# sch_mk32_dsd_2022-03-23.net
KiCad netlist of a schematic drawn in Altium Designer
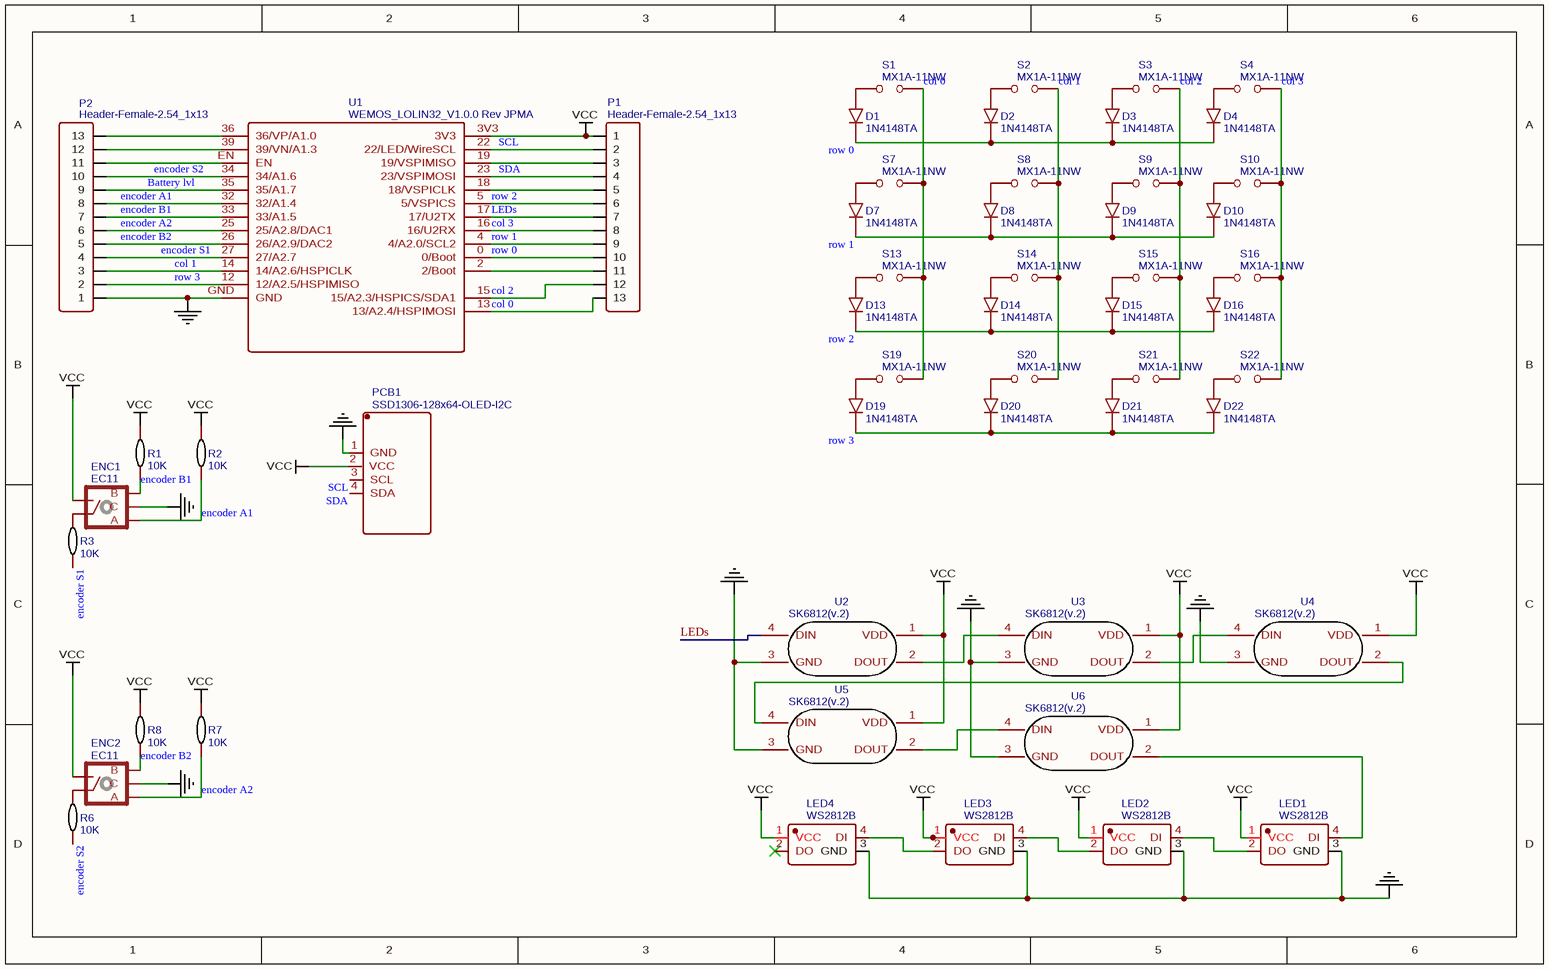
[diagram p0: sch_mk32_dsd_2022-03-23.schdoc]

(export (version "E")
  (design (tool "Eeschema 10.0.6"))
  (components
    (comp (ref "D1")
      (value "1N4148TA")
      (footprint "DO-35")
      (fields (field (name "BOM_SUPPLIER PART") "C124481") (field (name "CONTRIBUTOR") "LCSC"))
      (libsource (lib "altium-import") (part "root_3_1N4148TA_"))
    )
    (comp (ref "D2")
      (value "1N4148TA")
      (footprint "DO-35")
      (fields (field (name "BOM_SUPPLIER PART") "C124481") (field (name "CONTRIBUTOR") "LCSC"))
      (libsource (lib "altium-import") (part "root_3_1N4148TA_"))
    )
    (comp (ref "D3")
      (value "1N4148TA")
      (footprint "DO-35")
      (fields (field (name "BOM_SUPPLIER PART") "C124481") (field (name "CONTRIBUTOR") "LCSC"))
      (libsource (lib "altium-import") (part "root_3_1N4148TA_"))
    )
    (comp (ref "D4")
      (value "1N4148TA")
      (footprint "DO-35")
      (fields (field (name "BOM_SUPPLIER PART") "C124481") (field (name "CONTRIBUTOR") "LCSC"))
      (libsource (lib "altium-import") (part "root_3_1N4148TA_"))
    )
    (comp (ref "D7")
      (value "1N4148TA")
      (footprint "DO-35")
      (fields (field (name "BOM_SUPPLIER PART") "C124481") (field (name "CONTRIBUTOR") "LCSC"))
      (libsource (lib "altium-import") (part "root_3_1N4148TA_"))
    )
    (comp (ref "D8")
      (value "1N4148TA")
      (footprint "DO-35")
      (fields (field (name "BOM_SUPPLIER PART") "C124481") (field (name "CONTRIBUTOR") "LCSC"))
      (libsource (lib "altium-import") (part "root_3_1N4148TA_"))
    )
    (comp (ref "D9")
      (value "1N4148TA")
      (footprint "DO-35")
      (fields (field (name "BOM_SUPPLIER PART") "C124481") (field (name "CONTRIBUTOR") "LCSC"))
      (libsource (lib "altium-import") (part "root_3_1N4148TA_"))
    )
    (comp (ref "D10")
      (value "1N4148TA")
      (footprint "DO-35")
      (fields (field (name "BOM_SUPPLIER PART") "C124481") (field (name "CONTRIBUTOR") "LCSC"))
      (libsource (lib "altium-import") (part "root_3_1N4148TA_"))
    )
    (comp (ref "D13")
      (value "1N4148TA")
      (footprint "DO-35")
      (fields (field (name "BOM_SUPPLIER PART") "C124481") (field (name "CONTRIBUTOR") "LCSC"))
      (libsource (lib "altium-import") (part "root_3_1N4148TA_"))
    )
    (comp (ref "D14")
      (value "1N4148TA")
      (footprint "DO-35")
      (fields (field (name "BOM_SUPPLIER PART") "C124481") (field (name "CONTRIBUTOR") "LCSC"))
      (libsource (lib "altium-import") (part "root_3_1N4148TA_"))
    )
    (comp (ref "D15")
      (value "1N4148TA")
      (footprint "DO-35")
      (fields (field (name "BOM_SUPPLIER PART") "C124481") (field (name "CONTRIBUTOR") "LCSC"))
      (libsource (lib "altium-import") (part "root_3_1N4148TA_"))
    )
    (comp (ref "D16")
      (value "1N4148TA")
      (footprint "DO-35")
      (fields (field (name "BOM_SUPPLIER PART") "C124481") (field (name "CONTRIBUTOR") "LCSC"))
      (libsource (lib "altium-import") (part "root_3_1N4148TA_"))
    )
    (comp (ref "D19")
      (value "1N4148TA")
      (footprint "DO-35")
      (fields (field (name "BOM_SUPPLIER PART") "C124481") (field (name "CONTRIBUTOR") "LCSC"))
      (libsource (lib "altium-import") (part "root_3_1N4148TA_"))
    )
    (comp (ref "D20")
      (value "1N4148TA")
      (footprint "DO-35")
      (fields (field (name "BOM_SUPPLIER PART") "C124481") (field (name "CONTRIBUTOR") "LCSC"))
      (libsource (lib "altium-import") (part "root_3_1N4148TA_"))
    )
    (comp (ref "D21")
      (value "1N4148TA")
      (footprint "DO-35")
      (fields (field (name "BOM_SUPPLIER PART") "C124481") (field (name "CONTRIBUTOR") "LCSC"))
      (libsource (lib "altium-import") (part "root_3_1N4148TA_"))
    )
    (comp (ref "D22")
      (value "1N4148TA")
      (footprint "DO-35")
      (fields (field (name "BOM_SUPPLIER PART") "C124481") (field (name "CONTRIBUTOR") "LCSC"))
      (libsource (lib "altium-import") (part "root_3_1N4148TA_"))
    )
    (comp (ref "ENC1")
      (value "EC11")
      (footprint "EC11")
      (fields (field (name "BOM_MANUFACTURER PART") "?"))
      (libsource (lib "altium-import") (part "root_0_EC11_"))
    )
    (comp (ref "ENC2")
      (value "EC11")
      (footprint "EC11")
      (fields (field (name "BOM_MANUFACTURER PART") "?"))
      (libsource (lib "altium-import") (part "root_0_EC11_"))
    )
    (comp (ref "LED1")
      (value "WS2812B")
      (footprint "WS2812B-MIRROR")
      (fields (field (name "CONTRIBUTOR") "ridgy"))
      (libsource (lib "") (part "root_0_WS2812B__2"))
    )
    (comp (ref "LED2")
      (value "WS2812B")
      (footprint "WS2812B-MIRROR")
      (fields (field (name "CONTRIBUTOR") "ridgy"))
      (libsource (lib "altium-import") (part "root_0_WS2812B_"))
    )
    (comp (ref "LED3")
      (value "WS2812B")
      (footprint "WS2812B-MIRROR")
      (fields (field (name "CONTRIBUTOR") "ridgy"))
      (libsource (lib "") (part "root_0_WS2812B__1"))
    )
    (comp (ref "LED4")
      (value "WS2812B")
      (footprint "WS2812B-MIRROR")
      (fields (field (name "CONTRIBUTOR") "ridgy"))
      (libsource (lib "") (part "root_0_WS2812B__2"))
    )
    (comp (ref "P1")
      (value "Header-Female-2.54_1x13")
      (footprint "HDR-13X1/2.54")
      (fields
        (field (name "BOM_MANUFACTURER PART") "Female header 2.54-1*13P")
        (field (name "BOM_SUPPLIER PART") "C52709")
        (field (name "CONTRIBUTOR") "LCSC")
      )
      (libsource (lib "altium-import") (part "root_0_Header-Female-2.54_1x13_"))
    )
    (comp (ref "P2")
      (value "Header-Female-2.54_1x13")
      (footprint "HDR-13X1/2.54")
      (fields
        (field (name "BOM_MANUFACTURER PART") "Female header 2.54-1*13P")
        (field (name "BOM_SUPPLIER PART") "C52709")
        (field (name "CONTRIBUTOR") "LCSC")
      )
      (libsource (lib "altium-import") (part "root_2_Header-Female-2.54_1x13_"))
    )
    (comp (ref "PCB1")
      (value "SSD1306-128x64-OLED-I2C")
      (footprint "SSD1306_GNDVCC")
      (fields (field (name "BOM_MANUFACTURER PART") "?"))
      (libsource (lib "altium-import") (part "root_0_SSD1306-128x64-OLED-I2C_"))
    )
    (comp (ref "R1")
      (value "10K")
      (footprint "R03")
      (fields (field (name "BOM_MANUFACTURER PART") "?") (field (name "CONTRIBUTOR") "sorinfxdx"))
      (libsource (lib "altium-import") (part "root_0_10K_"))
    )
    (comp (ref "R2")
      (value "10K")
      (footprint "R03")
      (fields (field (name "BOM_MANUFACTURER PART") "?") (field (name "CONTRIBUTOR") "sorinfxdx"))
      (libsource (lib "altium-import") (part "root_0_10K_"))
    )
    (comp (ref "R3")
      (value "10K")
      (footprint "R03")
      (fields (field (name "BOM_MANUFACTURER PART") "?") (field (name "CONTRIBUTOR") "sorinfxdx"))
      (libsource (lib "altium-import") (part "root_0_10K_"))
    )
    (comp (ref "R6")
      (value "10K")
      (footprint "R03")
      (fields (field (name "BOM_MANUFACTURER PART") "?") (field (name "CONTRIBUTOR") "sorinfxdx"))
      (libsource (lib "altium-import") (part "root_0_10K_"))
    )
    (comp (ref "R7")
      (value "10K")
      (footprint "R03")
      (fields (field (name "BOM_MANUFACTURER PART") "?") (field (name "CONTRIBUTOR") "sorinfxdx"))
      (libsource (lib "altium-import") (part "root_0_10K_"))
    )
    (comp (ref "R8")
      (value "10K")
      (footprint "R03")
      (fields (field (name "BOM_MANUFACTURER PART") "?") (field (name "CONTRIBUTOR") "sorinfxdx"))
      (libsource (lib "altium-import") (part "root_0_10K_"))
    )
    (comp (ref "S1")
      (value "MX1A-11NW")
      (footprint "MX1A")
      (fields (field (name "BOM_SUPPLIER PART") "540-MX1A-11NW"))
      (libsource (lib "altium-import") (part "root_0_MX1A-11NW_"))
    )
    (comp (ref "S2")
      (value "MX1A-11NW")
      (footprint "MX1A")
      (fields (field (name "BOM_SUPPLIER PART") "540-MX1A-11NW"))
      (libsource (lib "altium-import") (part "root_0_MX1A-11NW_"))
    )
    (comp (ref "S3")
      (value "MX1A-11NW")
      (footprint "MX1A")
      (fields (field (name "BOM_SUPPLIER PART") "540-MX1A-11NW"))
      (libsource (lib "altium-import") (part "root_0_MX1A-11NW_"))
    )
    (comp (ref "S4")
      (value "MX1A-11NW")
      (footprint "MX1A")
      (fields (field (name "BOM_SUPPLIER PART") "540-MX1A-11NW"))
      (libsource (lib "altium-import") (part "root_0_MX1A-11NW_"))
    )
    (comp (ref "S7")
      (value "MX1A-11NW")
      (footprint "MX1A")
      (fields (field (name "BOM_SUPPLIER PART") "540-MX1A-11NW"))
      (libsource (lib "altium-import") (part "root_0_MX1A-11NW_"))
    )
    (comp (ref "S8")
      (value "MX1A-11NW")
      (footprint "MX1A")
      (fields (field (name "BOM_SUPPLIER PART") "540-MX1A-11NW"))
      (libsource (lib "altium-import") (part "root_0_MX1A-11NW_"))
    )
    (comp (ref "S9")
      (value "MX1A-11NW")
      (footprint "MX1A")
      (fields (field (name "BOM_SUPPLIER PART") "540-MX1A-11NW"))
      (libsource (lib "altium-import") (part "root_0_MX1A-11NW_"))
    )
    (comp (ref "S10")
      (value "MX1A-11NW")
      (footprint "MX1A")
      (fields (field (name "BOM_SUPPLIER PART") "540-MX1A-11NW"))
      (libsource (lib "altium-import") (part "root_0_MX1A-11NW_"))
    )
    (comp (ref "S13")
      (value "MX1A-11NW")
      (footprint "MX1A")
      (fields (field (name "BOM_SUPPLIER PART") "540-MX1A-11NW"))
      (libsource (lib "altium-import") (part "root_0_MX1A-11NW_"))
    )
    (comp (ref "S14")
      (value "MX1A-11NW")
      (footprint "MX1A")
      (fields (field (name "BOM_SUPPLIER PART") "540-MX1A-11NW"))
      (libsource (lib "altium-import") (part "root_0_MX1A-11NW_"))
    )
    (comp (ref "S15")
      (value "MX1A-11NW")
      (footprint "MX1A")
      (fields (field (name "BOM_SUPPLIER PART") "540-MX1A-11NW"))
      (libsource (lib "altium-import") (part "root_0_MX1A-11NW_"))
    )
    (comp (ref "S16")
      (value "MX1A-11NW")
      (footprint "MX1A")
      (fields (field (name "BOM_SUPPLIER PART") "540-MX1A-11NW"))
      (libsource (lib "altium-import") (part "root_0_MX1A-11NW_"))
    )
    (comp (ref "S19")
      (value "MX1A-11NW")
      (footprint "MX1A")
      (fields (field (name "BOM_SUPPLIER PART") "540-MX1A-11NW"))
      (libsource (lib "altium-import") (part "root_0_MX1A-11NW_"))
    )
    (comp (ref "S20")
      (value "MX1A-11NW")
      (footprint "MX1A")
      (fields (field (name "BOM_SUPPLIER PART") "540-MX1A-11NW"))
      (libsource (lib "altium-import") (part "root_0_MX1A-11NW_"))
    )
    (comp (ref "S21")
      (value "MX1A-11NW")
      (footprint "MX1A")
      (fields (field (name "BOM_SUPPLIER PART") "540-MX1A-11NW"))
      (libsource (lib "altium-import") (part "root_0_MX1A-11NW_"))
    )
    (comp (ref "S22")
      (value "MX1A-11NW")
      (footprint "MX1A")
      (fields (field (name "BOM_SUPPLIER PART") "540-MX1A-11NW"))
      (libsource (lib "altium-import") (part "root_0_MX1A-11NW_"))
    )
    (comp (ref "U1")
      (value "WEMOS_LOLIN32_V1.0.0 Rev JPMA")
      (footprint "WEMOS LOLIN32 LITE V1.0.0 UC")
      (fields (field (name "BOM_MANUFACTURER PART") "?") (field (name "CONTRIBUTOR") "JPMA"))
      (libsource (lib "altium-import") (part "root_0_WEMOS_LOLIN32_V1.0.0 Rev JPMA_"))
    )
    (comp (ref "U2")
      (value "SK6812(v.2)")
      (footprint "SK6812MINI-E")
      (fields (field (name "CONTRIBUTOR") "PetrSlachta"))
      (libsource (lib "altium-import") (part "root_0_SK6812(v.2)_"))
    )
    (comp (ref "U3")
      (value "SK6812(v.2)")
      (footprint "SK6812MINI-E")
      (fields (field (name "CONTRIBUTOR") "PetrSlachta"))
      (libsource (lib "altium-import") (part "root_0_SK6812(v.2)_"))
    )
    (comp (ref "U4")
      (value "SK6812(v.2)")
      (footprint "SK6812MINI-E")
      (fields (field (name "CONTRIBUTOR") "PetrSlachta"))
      (libsource (lib "altium-import") (part "root_0_SK6812(v.2)_"))
    )
    (comp (ref "U5")
      (value "SK6812(v.2)")
      (footprint "SK6812MINI-E")
      (fields (field (name "CONTRIBUTOR") "PetrSlachta"))
      (libsource (lib "altium-import") (part "root_0_SK6812(v.2)_"))
    )
    (comp (ref "U6")
      (value "SK6812(v.2)")
      (footprint "SK6812MINI-E")
      (fields (field (name "CONTRIBUTOR") "PetrSlachta"))
      (libsource (lib "altium-import") (part "root_0_SK6812(v.2)_"))
    )
  )
  (nets
    (net (code "1") (name "/Battery lvl") (class "Default")
      (node (ref "P2") (pin "9") (pinfunction "9_9") (pintype "passive"))
      (node (ref "U1") (pin "35") (pinfunction "35/A1.7_35") (pintype "passive"))
    )
    (net (code "2") (name "/LEDs") (class "Default")
      (node (ref "P1") (pin "7") (pinfunction "7_7") (pintype "passive"))
      (node (ref "U1") (pin "17") (pinfunction "17/U2TX_17") (pintype "passive"))
      (node (ref "U2") (pin "4") (pinfunction "DIN_4") (pintype "passive"))
    )
    (net (code "3") (name "/SCL") (class "Default")
      (node (ref "P1") (pin "2") (pinfunction "2_2") (pintype "passive"))
      (node (ref "PCB1") (pin "3") (pinfunction "SCL_3") (pintype "passive"))
      (node (ref "U1") (pin "22") (pinfunction "22/LED/WireSCL_22") (pintype "passive"))
    )
    (net (code "4") (name "/SDA") (class "Default")
      (node (ref "P1") (pin "4") (pinfunction "4_4") (pintype "passive"))
      (node (ref "PCB1") (pin "4") (pinfunction "SDA_4") (pintype "passive"))
      (node (ref "U1") (pin "23") (pinfunction "23/VSPIMOSI_23") (pintype "passive"))
    )
    (net (code "5") (name "/col 0") (class "Default")
      (node (ref "P1") (pin "13") (pinfunction "13_13") (pintype "passive"))
      (node (ref "S1") (pin "2") (pinfunction "2_2") (pintype "passive"))
      (node (ref "S13") (pin "2") (pinfunction "2_2") (pintype "passive"))
      (node (ref "S19") (pin "2") (pinfunction "2_2") (pintype "passive"))
      (node (ref "S7") (pin "2") (pinfunction "2_2") (pintype "passive"))
      (node (ref "U1") (pin "13") (pinfunction "13/A2.4/HSPIMOSI_13") (pintype "passive"))
    )
    (net (code "6") (name "/col 1") (class "Default")
      (node (ref "P2") (pin "3") (pinfunction "3_3") (pintype "passive"))
      (node (ref "S14") (pin "2") (pinfunction "2_2") (pintype "passive"))
      (node (ref "S2") (pin "2") (pinfunction "2_2") (pintype "passive"))
      (node (ref "S20") (pin "2") (pinfunction "2_2") (pintype "passive"))
      (node (ref "S8") (pin "2") (pinfunction "2_2") (pintype "passive"))
      (node (ref "U1") (pin "14") (pinfunction "14/A2.6/HSPICLK_14") (pintype "passive"))
    )
    (net (code "7") (name "/col 2") (class "Default")
      (node (ref "P1") (pin "12") (pinfunction "12_12") (pintype "passive"))
      (node (ref "S15") (pin "2") (pinfunction "2_2") (pintype "passive"))
      (node (ref "S21") (pin "2") (pinfunction "2_2") (pintype "passive"))
      (node (ref "S3") (pin "2") (pinfunction "2_2") (pintype "passive"))
      (node (ref "S9") (pin "2") (pinfunction "2_2") (pintype "passive"))
      (node (ref "U1") (pin "15") (pinfunction "15/A2.3/HSPICS/SDA1_15") (pintype "passive"))
    )
    (net (code "8") (name "/col 3") (class "Default")
      (node (ref "P1") (pin "8") (pinfunction "8_8") (pintype "passive"))
      (node (ref "S10") (pin "2") (pinfunction "2_2") (pintype "passive"))
      (node (ref "S16") (pin "2") (pinfunction "2_2") (pintype "passive"))
      (node (ref "S22") (pin "2") (pinfunction "2_2") (pintype "passive"))
      (node (ref "S4") (pin "2") (pinfunction "2_2") (pintype "passive"))
      (node (ref "U1") (pin "16") (pinfunction "16/U2RX_16") (pintype "passive"))
    )
    (net (code "9") (name "/encoder A1") (class "Default")
      (node (ref "ENC1") (pin "3") (pinfunction "A_3") (pintype "passive"))
      (node (ref "P2") (pin "8") (pinfunction "8_8") (pintype "passive"))
      (node (ref "R2") (pin "2") (pinfunction "2_2") (pintype "passive"))
      (node (ref "U1") (pin "32") (pinfunction "32/A1.4_32") (pintype "passive"))
    )
    (net (code "10") (name "/encoder A2") (class "Default")
      (node (ref "ENC2") (pin "3") (pinfunction "A_3") (pintype "passive"))
      (node (ref "P2") (pin "6") (pinfunction "6_6") (pintype "passive"))
      (node (ref "R7") (pin "2") (pinfunction "2_2") (pintype "passive"))
      (node (ref "U1") (pin "25") (pinfunction "25/A2.8/DAC1_25") (pintype "passive"))
    )
    (net (code "11") (name "/encoder B1") (class "Default")
      (node (ref "ENC1") (pin "4") (pinfunction "B_4") (pintype "passive"))
      (node (ref "P2") (pin "7") (pinfunction "7_7") (pintype "passive"))
      (node (ref "R1") (pin "2") (pinfunction "2_2") (pintype "passive"))
      (node (ref "U1") (pin "33") (pinfunction "33/A1.5_33") (pintype "passive"))
    )
    (net (code "12") (name "/encoder B2") (class "Default")
      (node (ref "ENC2") (pin "4") (pinfunction "B_4") (pintype "passive"))
      (node (ref "P2") (pin "5") (pinfunction "5_5") (pintype "passive"))
      (node (ref "R8") (pin "2") (pinfunction "2_2") (pintype "passive"))
      (node (ref "U1") (pin "26") (pinfunction "26/A2.9/DAC2_26") (pintype "passive"))
    )
    (net (code "13") (name "/encoder S1") (class "Default")
      (node (ref "P2") (pin "4") (pinfunction "4_4") (pintype "passive"))
      (node (ref "R3") (pin "2") (pinfunction "2_2") (pintype "passive"))
      (node (ref "U1") (pin "27") (pinfunction "27/A2.7_27") (pintype "passive"))
    )
    (net (code "14") (name "/encoder S2") (class "Default")
      (node (ref "P2") (pin "10") (pinfunction "10_10") (pintype "passive"))
      (node (ref "R6") (pin "2") (pinfunction "2_2") (pintype "passive"))
      (node (ref "U1") (pin "34") (pinfunction "34/A1.6_34") (pintype "passive"))
    )
    (net (code "15") (name "/row 0") (class "Default")
      (node (ref "D1") (pin "2") (pinfunction "2_2") (pintype "passive"))
      (node (ref "D2") (pin "2") (pinfunction "2_2") (pintype "passive"))
      (node (ref "D3") (pin "2") (pinfunction "2_2") (pintype "passive"))
      (node (ref "D4") (pin "2") (pinfunction "2_2") (pintype "passive"))
      (node (ref "P1") (pin "10") (pinfunction "10_10") (pintype "passive"))
      (node (ref "U1") (pin "0") (pinfunction "0/Boot_0") (pintype "passive"))
    )
    (net (code "16") (name "/row 1") (class "Default")
      (node (ref "D10") (pin "2") (pinfunction "2_2") (pintype "passive"))
      (node (ref "D7") (pin "2") (pinfunction "2_2") (pintype "passive"))
      (node (ref "D8") (pin "2") (pinfunction "2_2") (pintype "passive"))
      (node (ref "D9") (pin "2") (pinfunction "2_2") (pintype "passive"))
      (node (ref "P1") (pin "9") (pinfunction "9_9") (pintype "passive"))
      (node (ref "U1") (pin "4") (pinfunction "4/A2.0/SCL2_4") (pintype "passive"))
    )
    (net (code "17") (name "/row 2") (class "Default")
      (node (ref "D13") (pin "2") (pinfunction "2_2") (pintype "passive"))
      (node (ref "D14") (pin "2") (pinfunction "2_2") (pintype "passive"))
      (node (ref "D15") (pin "2") (pinfunction "2_2") (pintype "passive"))
      (node (ref "D16") (pin "2") (pinfunction "2_2") (pintype "passive"))
      (node (ref "P1") (pin "6") (pinfunction "6_6") (pintype "passive"))
      (node (ref "U1") (pin "5") (pinfunction "5/VSPICS_5") (pintype "passive"))
    )
    (net (code "18") (name "/row 3") (class "Default")
      (node (ref "D19") (pin "2") (pinfunction "2_2") (pintype "passive"))
      (node (ref "D20") (pin "2") (pinfunction "2_2") (pintype "passive"))
      (node (ref "D21") (pin "2") (pinfunction "2_2") (pintype "passive"))
      (node (ref "D22") (pin "2") (pinfunction "2_2") (pintype "passive"))
      (node (ref "P2") (pin "2") (pinfunction "2_2") (pintype "passive"))
      (node (ref "U1") (pin "12") (pinfunction "12/A2.5/HSPIMISO_12") (pintype "passive"))
    )
    (net (code "19") (name "GND") (class "Default")
      (node (ref "ENC1") (pin "5") (pinfunction "C_5") (pintype "passive"))
      (node (ref "ENC2") (pin "5") (pinfunction "C_5") (pintype "passive"))
      (node (ref "LED1") (pin "3") (pinfunction "GND_3") (pintype "passive"))
      (node (ref "LED2") (pin "3") (pinfunction "GND_3") (pintype "passive"))
      (node (ref "LED3") (pin "3") (pinfunction "GND_3") (pintype "passive"))
      (node (ref "LED4") (pin "3") (pinfunction "GND_3") (pintype "passive"))
      (node (ref "P2") (pin "1") (pinfunction "1_1") (pintype "passive"))
      (node (ref "PCB1") (pin "1") (pinfunction "GND_1") (pintype "passive"))
      (node (ref "U1") (pin "GND") (pinfunction "GND_GND") (pintype "passive"))
      (node (ref "U2") (pin "3") (pinfunction "GND_3") (pintype "passive"))
      (node (ref "U3") (pin "3") (pinfunction "GND_3") (pintype "passive"))
      (node (ref "U4") (pin "3") (pinfunction "GND_3") (pintype "passive"))
      (node (ref "U5") (pin "3") (pinfunction "GND_3") (pintype "passive"))
      (node (ref "U6") (pin "3") (pinfunction "GND_3") (pintype "passive"))
    )
    (net (code "20") (name "Net-(D1-Pad1)") (class "Default")
      (node (ref "D1") (pin "1") (pinfunction "1_1") (pintype "passive"))
      (node (ref "S1") (pin "1") (pinfunction "1_1") (pintype "passive"))
    )
    (net (code "21") (name "Net-(D2-Pad1)") (class "Default")
      (node (ref "D2") (pin "1") (pinfunction "1_1") (pintype "passive"))
      (node (ref "S2") (pin "1") (pinfunction "1_1") (pintype "passive"))
    )
    (net (code "22") (name "Net-(D3-Pad1)") (class "Default")
      (node (ref "D3") (pin "1") (pinfunction "1_1") (pintype "passive"))
      (node (ref "S3") (pin "1") (pinfunction "1_1") (pintype "passive"))
    )
    (net (code "23") (name "Net-(D4-Pad1)") (class "Default")
      (node (ref "D4") (pin "1") (pinfunction "1_1") (pintype "passive"))
      (node (ref "S4") (pin "1") (pinfunction "1_1") (pintype "passive"))
    )
    (net (code "24") (name "Net-(D7-Pad1)") (class "Default")
      (node (ref "D7") (pin "1") (pinfunction "1_1") (pintype "passive"))
      (node (ref "S7") (pin "1") (pinfunction "1_1") (pintype "passive"))
    )
    (net (code "25") (name "Net-(D8-Pad1)") (class "Default")
      (node (ref "D8") (pin "1") (pinfunction "1_1") (pintype "passive"))
      (node (ref "S8") (pin "1") (pinfunction "1_1") (pintype "passive"))
    )
    (net (code "26") (name "Net-(D9-Pad1)") (class "Default")
      (node (ref "D9") (pin "1") (pinfunction "1_1") (pintype "passive"))
      (node (ref "S9") (pin "1") (pinfunction "1_1") (pintype "passive"))
    )
    (net (code "27") (name "Net-(D10-Pad1)") (class "Default")
      (node (ref "D10") (pin "1") (pinfunction "1_1") (pintype "passive"))
      (node (ref "S10") (pin "1") (pinfunction "1_1") (pintype "passive"))
    )
    (net (code "28") (name "Net-(D13-Pad1)") (class "Default")
      (node (ref "D13") (pin "1") (pinfunction "1_1") (pintype "passive"))
      (node (ref "S13") (pin "1") (pinfunction "1_1") (pintype "passive"))
    )
    (net (code "29") (name "Net-(D14-Pad1)") (class "Default")
      (node (ref "D14") (pin "1") (pinfunction "1_1") (pintype "passive"))
      (node (ref "S14") (pin "1") (pinfunction "1_1") (pintype "passive"))
    )
    (net (code "30") (name "Net-(D15-Pad1)") (class "Default")
      (node (ref "D15") (pin "1") (pinfunction "1_1") (pintype "passive"))
      (node (ref "S15") (pin "1") (pinfunction "1_1") (pintype "passive"))
    )
    (net (code "31") (name "Net-(D16-Pad1)") (class "Default")
      (node (ref "D16") (pin "1") (pinfunction "1_1") (pintype "passive"))
      (node (ref "S16") (pin "1") (pinfunction "1_1") (pintype "passive"))
    )
    (net (code "32") (name "Net-(D19-Pad1)") (class "Default")
      (node (ref "D19") (pin "1") (pinfunction "1_1") (pintype "passive"))
      (node (ref "S19") (pin "1") (pinfunction "1_1") (pintype "passive"))
    )
    (net (code "33") (name "Net-(D20-Pad1)") (class "Default")
      (node (ref "D20") (pin "1") (pinfunction "1_1") (pintype "passive"))
      (node (ref "S20") (pin "1") (pinfunction "1_1") (pintype "passive"))
    )
    (net (code "34") (name "Net-(D21-Pad1)") (class "Default")
      (node (ref "D21") (pin "1") (pinfunction "1_1") (pintype "passive"))
      (node (ref "S21") (pin "1") (pinfunction "1_1") (pintype "passive"))
    )
    (net (code "35") (name "Net-(D22-Pad1)") (class "Default")
      (node (ref "D22") (pin "1") (pinfunction "1_1") (pintype "passive"))
      (node (ref "S22") (pin "1") (pinfunction "1_1") (pintype "passive"))
    )
    (net (code "36") (name "Net-(ENC1-Pad1)") (class "Default")
      (node (ref "ENC1") (pin "1") (pinfunction "1_1") (pintype "passive"))
      (node (ref "R3") (pin "1") (pinfunction "1_1") (pintype "passive"))
    )
    (net (code "37") (name "Net-(ENC2-Pad1)") (class "Default")
      (node (ref "ENC2") (pin "1") (pinfunction "1_1") (pintype "passive"))
      (node (ref "R6") (pin "1") (pinfunction "1_1") (pintype "passive"))
    )
    (net (code "38") (name "Net-(LED1-DI)") (class "Default")
      (node (ref "LED1") (pin "4") (pinfunction "DI_4") (pintype "passive"))
      (node (ref "U6") (pin "2") (pinfunction "DOUT_2") (pintype "passive"))
    )
    (net (code "39") (name "Net-(LED1-DO)") (class "Default")
      (node (ref "LED1") (pin "2") (pinfunction "DO_2") (pintype "passive"))
      (node (ref "LED2") (pin "4") (pinfunction "DI_4") (pintype "passive"))
    )
    (net (code "40") (name "Net-(LED2-DO)") (class "Default")
      (node (ref "LED2") (pin "2") (pinfunction "DO_2") (pintype "passive"))
      (node (ref "LED3") (pin "4") (pinfunction "DI_4") (pintype "passive"))
    )
    (net (code "41") (name "Net-(LED3-DO)") (class "Default")
      (node (ref "LED3") (pin "2") (pinfunction "DO_2") (pintype "passive"))
      (node (ref "LED4") (pin "4") (pinfunction "DI_4") (pintype "passive"))
    )
    (net (code "42") (name "Net-(P2-Pad11)") (class "Default")
      (node (ref "P2") (pin "11") (pinfunction "11_11") (pintype "passive"))
      (node (ref "U1") (pin "EN") (pinfunction "EN_EN") (pintype "passive"))
    )
    (net (code "43") (name "Net-(U1-2{slash}Boot)") (class "Default")
      (node (ref "P1") (pin "11") (pinfunction "11_11") (pintype "passive"))
      (node (ref "U1") (pin "2") (pinfunction "2/Boot_2") (pintype "passive"))
    )
    (net (code "44") (name "Net-(U1-18{slash}VSPICLK)") (class "Default")
      (node (ref "P1") (pin "5") (pinfunction "5_5") (pintype "passive"))
      (node (ref "U1") (pin "18") (pinfunction "18/VSPICLK_18") (pintype "passive"))
    )
    (net (code "45") (name "Net-(U1-19{slash}VSPIMISO)") (class "Default")
      (node (ref "P1") (pin "3") (pinfunction "3_3") (pintype "passive"))
      (node (ref "U1") (pin "19") (pinfunction "19/VSPIMISO_19") (pintype "passive"))
    )
    (net (code "46") (name "Net-(U1-36{slash}VP{slash}A1.0)") (class "Default")
      (node (ref "P2") (pin "13") (pinfunction "13_13") (pintype "passive"))
      (node (ref "U1") (pin "36") (pinfunction "36/VP/A1.0_36") (pintype "passive"))
    )
    (net (code "47") (name "Net-(U1-39{slash}VN{slash}A1.3)") (class "Default")
      (node (ref "P2") (pin "12") (pinfunction "12_12") (pintype "passive"))
      (node (ref "U1") (pin "39") (pinfunction "39/VN/A1.3_39") (pintype "passive"))
    )
    (net (code "48") (name "Net-(U2-DOUT)") (class "Default")
      (node (ref "U2") (pin "2") (pinfunction "DOUT_2") (pintype "passive"))
      (node (ref "U3") (pin "4") (pinfunction "DIN_4") (pintype "passive"))
    )
    (net (code "49") (name "Net-(U3-DOUT)") (class "Default")
      (node (ref "U3") (pin "2") (pinfunction "DOUT_2") (pintype "passive"))
      (node (ref "U4") (pin "4") (pinfunction "DIN_4") (pintype "passive"))
    )
    (net (code "50") (name "Net-(U4-DOUT)") (class "Default")
      (node (ref "U4") (pin "2") (pinfunction "DOUT_2") (pintype "passive"))
      (node (ref "U5") (pin "4") (pinfunction "DIN_4") (pintype "passive"))
    )
    (net (code "51") (name "Net-(U5-DOUT)") (class "Default")
      (node (ref "U5") (pin "2") (pinfunction "DOUT_2") (pintype "passive"))
      (node (ref "U6") (pin "4") (pinfunction "DIN_4") (pintype "passive"))
    )
    (net (code "52") (name "VCC") (class "Default")
      (node (ref "ENC1") (pin "2") (pinfunction "2_2") (pintype "passive"))
      (node (ref "ENC2") (pin "2") (pinfunction "2_2") (pintype "passive"))
      (node (ref "LED1") (pin "1") (pinfunction "VCC_1") (pintype "passive"))
      (node (ref "LED2") (pin "1") (pinfunction "VCC_1") (pintype "passive"))
      (node (ref "LED3") (pin "1") (pinfunction "VCC_1") (pintype "passive"))
      (node (ref "LED4") (pin "1") (pinfunction "VCC_1") (pintype "passive"))
      (node (ref "P1") (pin "1") (pinfunction "1_1") (pintype "passive"))
      (node (ref "PCB1") (pin "2") (pinfunction "VCC_2") (pintype "passive"))
      (node (ref "R1") (pin "1") (pinfunction "1_1") (pintype "passive"))
      (node (ref "R2") (pin "1") (pinfunction "1_1") (pintype "passive"))
      (node (ref "R7") (pin "1") (pinfunction "1_1") (pintype "passive"))
      (node (ref "R8") (pin "1") (pinfunction "1_1") (pintype "passive"))
      (node (ref "U1") (pin "3V3") (pinfunction "3V3_3V3") (pintype "passive"))
      (node (ref "U2") (pin "1") (pinfunction "VDD_1") (pintype "passive"))
      (node (ref "U3") (pin "1") (pinfunction "VDD_1") (pintype "passive"))
      (node (ref "U4") (pin "1") (pinfunction "VDD_1") (pintype "passive"))
      (node (ref "U5") (pin "1") (pinfunction "VDD_1") (pintype "passive"))
      (node (ref "U6") (pin "1") (pinfunction "VDD_1") (pintype "passive"))
    )
    (net (code "53") (name "unconnected-(LED4-DO-Pad2)") (class "Default")
      (node (ref "LED4") (pin "2") (pinfunction "DO_2") (pintype "passive+no_connect"))
    )
  )
)
